# fan.net
KiCad netlist of a schematic drawn in EasyEDA Pro
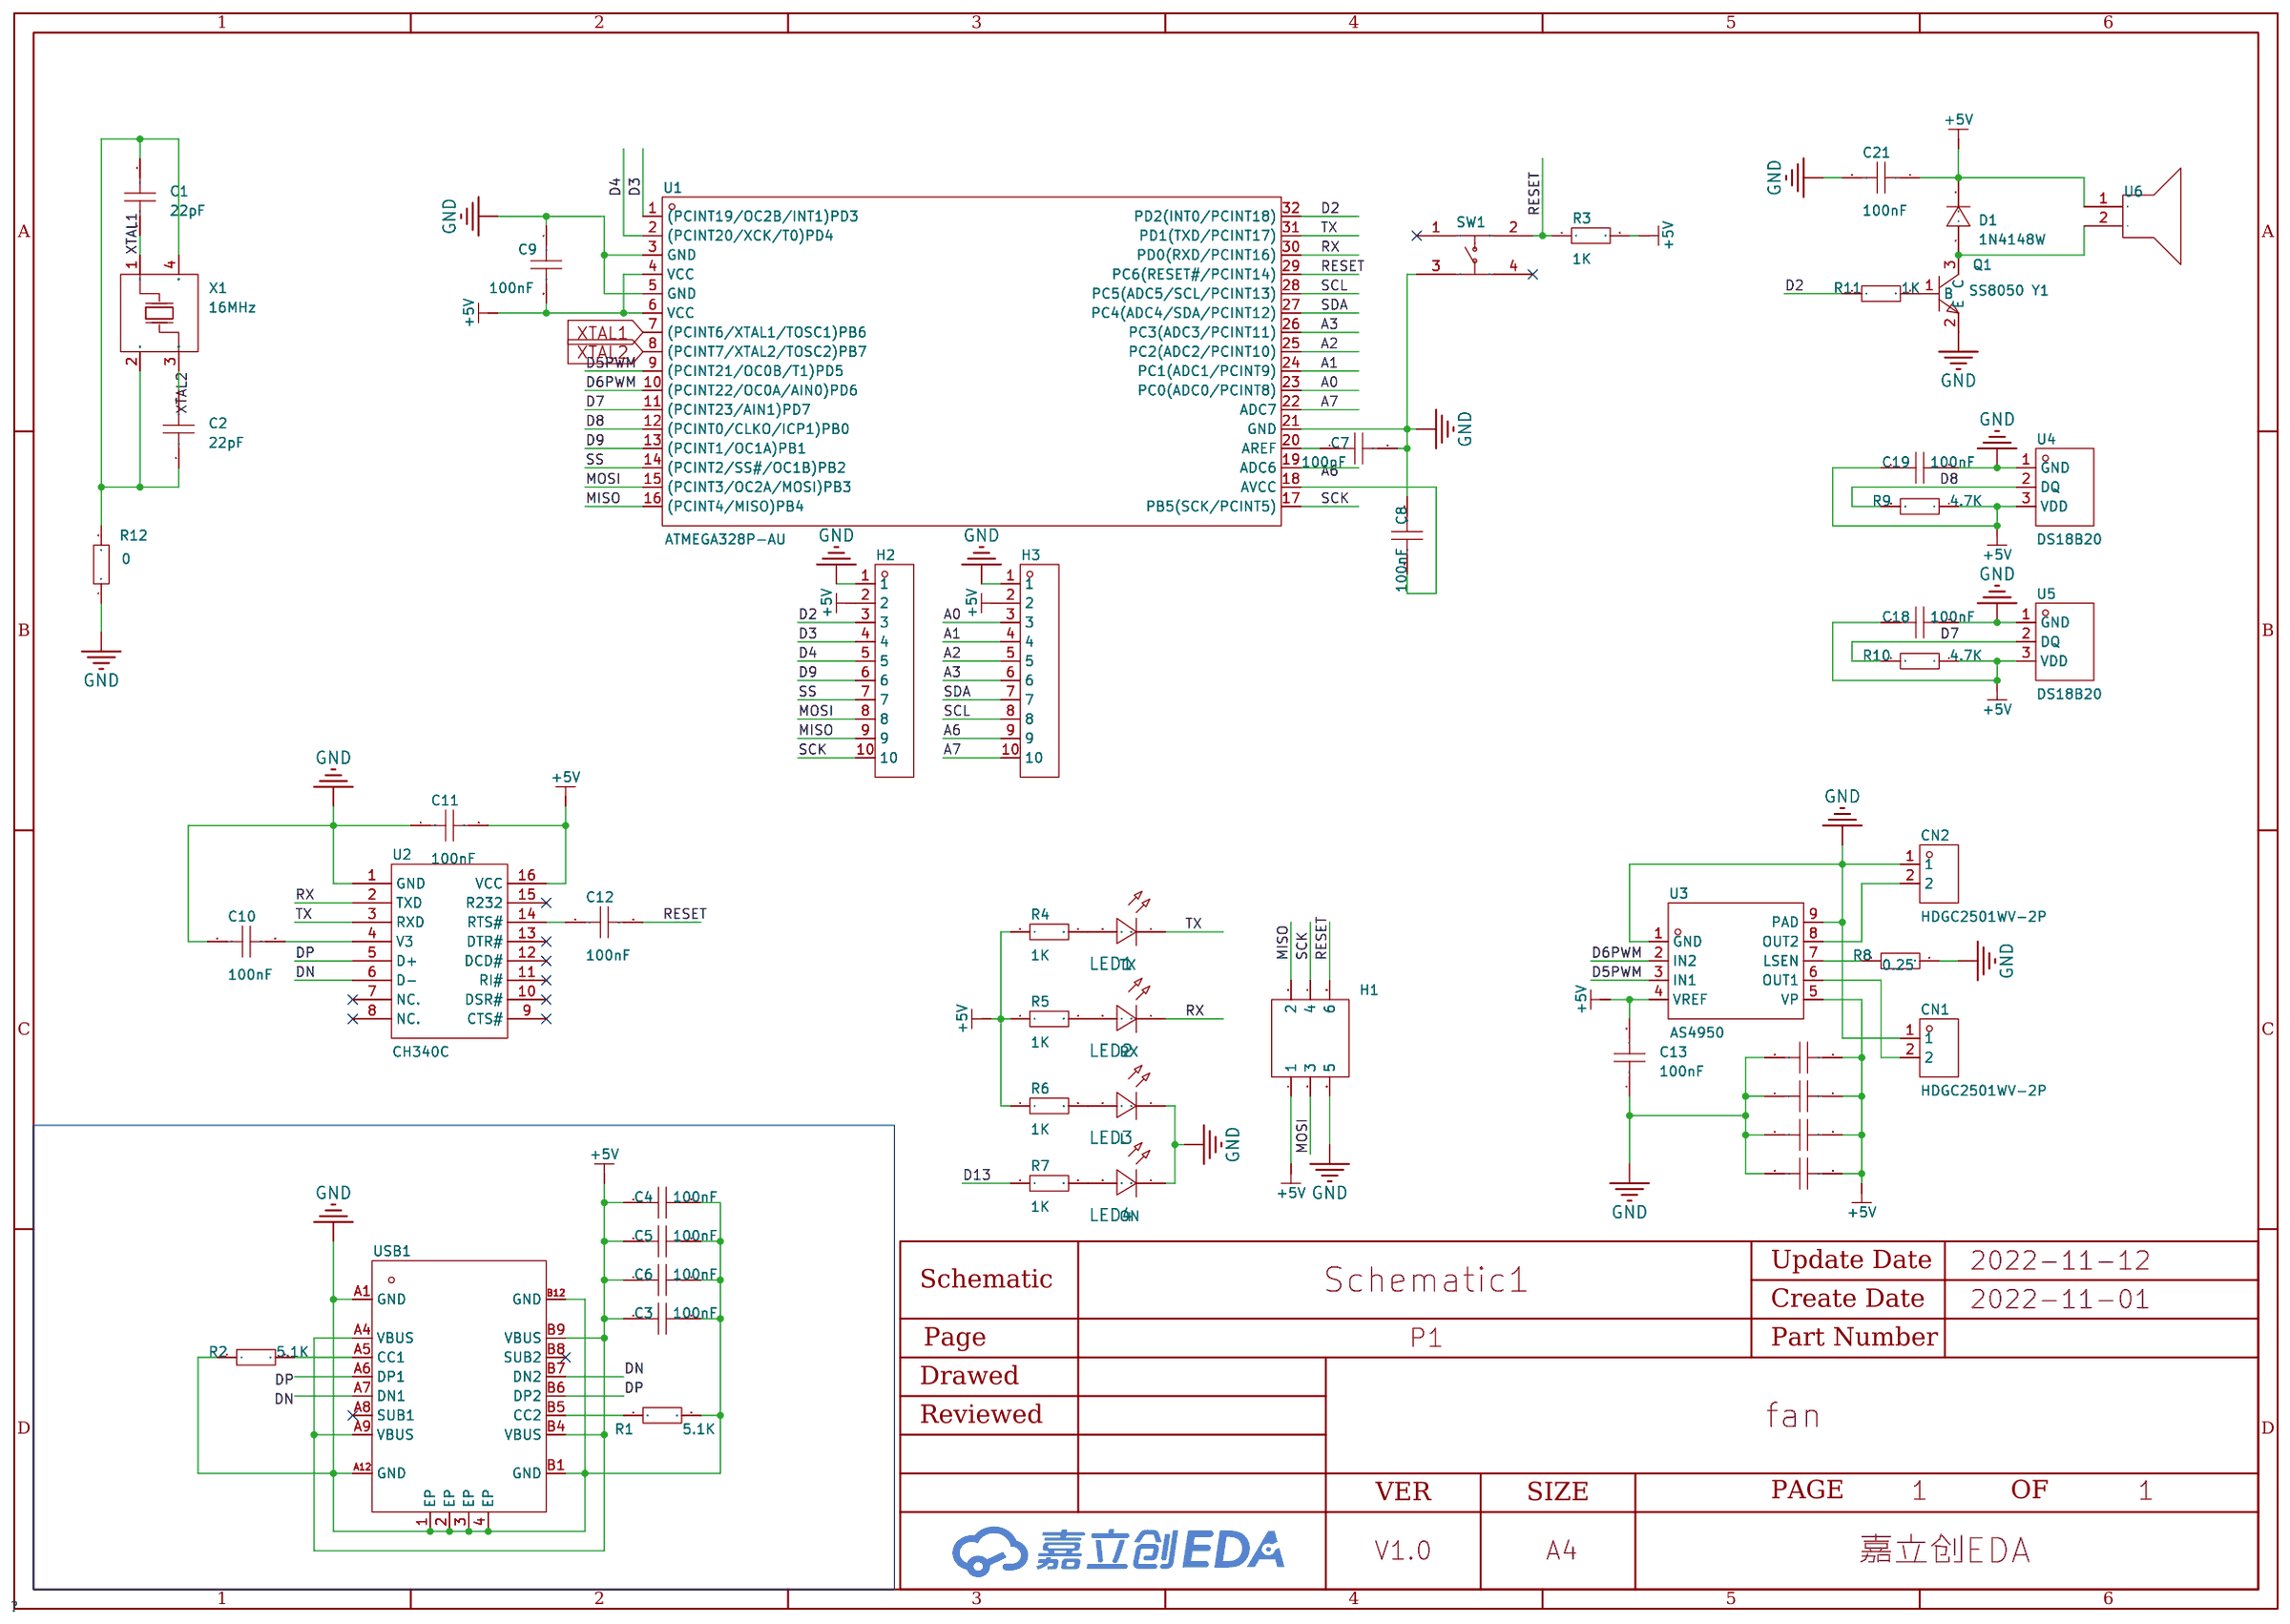
[diagram p0: schematic sheet]

(export (version "E")
  (design (tool "Eeschema 10.0.6"))
  (components
    (comp (ref "C1")
      (value "100nF")
      (footprint "easyedapro:C0603")
      (libsource (lib "easyedapro") (part "C1210X7R475K630NT"))
    )
    (comp (ref "C2")
      (value "100nF")
      (footprint "easyedapro:C0603")
      (libsource (lib "easyedapro") (part "C1210X7R475K630NT"))
    )
    (comp (ref "C3")
      (value "100nF")
      (footprint "easyedapro:C0603")
      (libsource (lib "easyedapro") (part "C1210X7R475K630NT"))
    )
    (comp (ref "C4")
      (value "100nF")
      (footprint "easyedapro:C0603")
      (libsource (lib "easyedapro") (part "C1210X7R475K630NT"))
    )
    (comp (ref "C5")
      (value "100nF")
      (footprint "easyedapro:C0603")
      (libsource (lib "easyedapro") (part "C1210X7R475K630NT"))
    )
    (comp (ref "C6")
      (value "100nF")
      (footprint "easyedapro:C0603")
      (libsource (lib "easyedapro") (part "C1210X7R475K630NT"))
    )
    (comp (ref "C7")
      (value "100nF")
      (footprint "easyedapro:C0603")
      (libsource (lib "easyedapro") (part "C1210X7R475K630NT"))
    )
    (comp (ref "C8")
      (value "100nF")
      (footprint "easyedapro:C0603")
      (libsource (lib "easyedapro") (part "C1210X7R475K630NT"))
    )
    (comp (ref "C9")
      (value "100nF")
      (footprint "easyedapro:C0603")
      (libsource (lib "easyedapro") (part "C1210X7R475K630NT"))
    )
    (comp (ref "C10")
      (value "100nF")
      (footprint "easyedapro:C0603")
      (libsource (lib "easyedapro") (part "C1210X7R475K630NT"))
    )
    (comp (ref "C11")
      (value "100nF")
      (footprint "easyedapro:C0603")
      (libsource (lib "easyedapro") (part "C1210X7R475K630NT"))
    )
    (comp (ref "C12")
      (value "100nF")
      (footprint "easyedapro:C0603")
      (libsource (lib "easyedapro") (part "C1210X7R475K630NT"))
    )
    (comp (ref "C13")
      (value "100nF")
      (footprint "easyedapro:C0603")
      (libsource (lib "easyedapro") (part "C1210X7R475K630NT"))
    )
    (comp (ref "C14")
      (value "100nF")
      (footprint "easyedapro:C0603")
      (libsource (lib "easyedapro") (part "C1210X7R475K630NT"))
    )
    (comp (ref "C15")
      (value "100nF")
      (footprint "easyedapro:C0603")
      (libsource (lib "easyedapro") (part "C1210X7R475K630NT"))
    )
    (comp (ref "C16")
      (value "100nF")
      (footprint "easyedapro:C0603")
      (libsource (lib "easyedapro") (part "C1210X7R475K630NT"))
    )
    (comp (ref "C17")
      (value "100nF")
      (footprint "easyedapro:C0603")
      (libsource (lib "easyedapro") (part "C1210X7R475K630NT"))
    )
    (comp (ref "C18")
      (value "100nF")
      (footprint "easyedapro:C0603")
      (libsource (lib "easyedapro") (part "C1210X7R475K630NT"))
    )
    (comp (ref "C19")
      (value "100nF")
      (footprint "easyedapro:C0603")
      (libsource (lib "easyedapro") (part "C1210X7R475K630NT"))
    )
    (comp (ref "C21")
      (value "100nF")
      (footprint "easyedapro:C0603")
      (libsource (lib "easyedapro") (part "C1210X7R475K630NT"))
    )
    (comp (ref "CN1")
      (value "HDGC2501WV-2P")
      (footprint "easyedapro:CONN-TH_XH2.5-2P")
      (fields (field (name "Manufacturer") "HDGC(华德共创)"))
      (libsource (lib "easyedapro") (part "HDGC2501WV-2P"))
    )
    (comp (ref "CN2")
      (value "HDGC2501WV-2P")
      (footprint "easyedapro:CONN-TH_XH2.5-2P")
      (fields (field (name "Manufacturer") "HDGC(华德共创)"))
      (libsource (lib "easyedapro") (part "HDGC2501WV-2P"))
    )
    (comp (ref "D1")
      (value "1N4148W")
      (footprint "easyedapro:SOD-123_L2.8-W1.8-LS3.7-RD")
      (fields (field (name "Manufacturer") "CJ（江苏长电/长晶）"))
      (libsource (lib "easyedapro") (part "1N4148W T4"))
    )
    (comp (ref "H1")
      (value "~")
      (footprint "easyedapro:HDR-TH_6P-P2.54-V-R2-C3-S2.54_A2541WV-2X3P")
      (libsource (lib "easyedapro") (part "HDR-M-2.54_2x3"))
    )
    (comp (ref "H2")
      (value "~")
      (footprint "easyedapro:HDR-TH_10P-P2.54-V-F")
      (libsource (lib "easyedapro") (part "X5511FV-10-C70D30-1000"))
    )
    (comp (ref "H3")
      (value "~")
      (footprint "easyedapro:HDR-TH_10P-P2.54-V-F")
      (libsource (lib "easyedapro") (part "X5511FV-10-C70D30-1000"))
    )
    (comp (ref "LED1")
      (value "TX")
      (footprint "easyedapro:LED0603-RD_BLUE")
      (libsource (lib "easyedapro") (part "LED_R"))
    )
    (comp (ref "LED2")
      (value "RX")
      (footprint "easyedapro:LED0603-RD_BLUE")
      (libsource (lib "easyedapro") (part "LED_R"))
    )
    (comp (ref "LED3")
      (value "L")
      (footprint "easyedapro:LED0603-RD_BLUE")
      (libsource (lib "easyedapro") (part "LED_R"))
    )
    (comp (ref "LED4")
      (value "ON")
      (footprint "easyedapro:LED0603-RD_BLUE")
      (libsource (lib "easyedapro") (part "LED_R"))
    )
    (comp (ref "Q1")
      (value "SS8050 Y1")
      (footprint "easyedapro:SOT-23-3_L2.9-W1.3-P1.90-LS2.4-BR")
      (fields (field (name "Manufacturer") "FOSAN(富信)"))
      (libsource (lib "easyedapro") (part "SS8050_C2926167"))
    )
    (comp (ref "R1") (value "10K") (footprint "easyedapro:R0603") (libsource (lib "easyedapro") (part "电阻")))
    (comp (ref "R2") (value "10K") (footprint "easyedapro:R0603") (libsource (lib "easyedapro") (part "电阻")))
    (comp (ref "R3") (value "10K") (footprint "easyedapro:R0603") (libsource (lib "easyedapro") (part "电阻")))
    (comp (ref "R4") (value "10K") (footprint "easyedapro:R0603") (libsource (lib "easyedapro") (part "电阻")))
    (comp (ref "R5") (value "10K") (footprint "easyedapro:R0603") (libsource (lib "easyedapro") (part "电阻")))
    (comp (ref "R6") (value "10K") (footprint "easyedapro:R0603") (libsource (lib "easyedapro") (part "电阻")))
    (comp (ref "R7") (value "10K") (footprint "easyedapro:R0603") (libsource (lib "easyedapro") (part "电阻")))
    (comp (ref "R8") (value "10K") (footprint "easyedapro:R0603") (libsource (lib "easyedapro") (part "电阻")))
    (comp (ref "R9") (value "10K") (footprint "easyedapro:R0603") (libsource (lib "easyedapro") (part "电阻")))
    (comp (ref "R10") (value "10K") (footprint "easyedapro:R0603") (libsource (lib "easyedapro") (part "电阻")))
    (comp (ref "R11") (value "10K") (footprint "easyedapro:R0603") (libsource (lib "easyedapro") (part "电阻")))
    (comp (ref "R12") (value "10K") (footprint "easyedapro:R0603") (libsource (lib "easyedapro") (part "电阻")))
    (comp (ref "SW1")
      (value "TSC015A03518A")
      (footprint "easyedapro:KEY-SMD_4P-L4.5-W4.5-P3.00-LS6.9")
      (description "触点电流:50mA;额定电压(AC):12V;额定电压(DC):12V;安装方式:立贴;按钮形状:圆形按钮;开关长度:4.5mm;开关宽度:4.5mm;开关高度:3.5mm;")
      (fields (field (name "Manufacturer") "BZCN(博众电气)"))
      (libsource (lib "easyedapro") (part "TSC015A03518A"))
    )
    (comp (ref "U1")
      (value "ATMEGA328P-AU")
      (footprint "easyedapro:TQFP-32_L7.0-W7.0-P0.80-LS9.0-BL")
      (description "ATmega Series 20 MHz 32 KB Flash 2 KB SRAM 8-Bit Microcontroller - TQFP-32")
      (fields (field (name "Manufacturer") "MICROCHIP(美国微芯)"))
      (libsource (lib "easyedapro") (part "ATMEGA328P-AU"))
    )
    (comp (ref "U2")
      (value "CH340C")
      (footprint "easyedapro:SOP-16_L10.0-W3.9-P1.27-LS6.0-BL")
      (description "类型:Transceiver;协议类别:USB 2.0;驱动器/接收器数:-;数据速率:2Mbps;")
      (fields (field (name "Manufacturer") "WCH(南京沁恒)"))
      (libsource (lib "easyedapro") (part "CH340C"))
    )
    (comp (ref "U3")
      (value "AS4950")
      (footprint "easyedapro:ESOP-8_L4.9-W3.9-P1.27-LS6.0-BL-EP")
      (description "全桥DMOS有刷直流电机驱动器，3.5A峰值驱动输出，8V-40V宽电压供电，支持过流/短路/欠压/过温保护")
      (fields (field (name "Manufacturer") "ASSEMSTAR(聚迹)"))
      (libsource (lib "easyedapro") (part "AS4950"))
    )
    (comp (ref "U4")
      (value "DS18B20")
      (footprint "easyedapro:TO-92-3_L4.9-W3.7-P1.27-L")
      (description "传感器类型:-;输出类型:-;局部感温:-;远程感温:-;分辨率:-;")
      (fields (field (name "Manufacturer") "UMW(友台半导体)"))
      (libsource (lib "easyedapro") (part "DS18B20"))
    )
    (comp (ref "U5")
      (value "DS18B20")
      (footprint "easyedapro:TO-92-3_L4.9-W3.7-P1.27-L")
      (description "传感器类型:-;输出类型:-;局部感温:-;远程感温:-;分辨率:-;")
      (fields (field (name "Manufacturer") "UMW(友台半导体)"))
      (libsource (lib "easyedapro") (part "DS18B20"))
    )
    (comp (ref "U6")
      (value "SFN-1270-0540-35P5.0")
      (footprint "easyedapro:BUZ-TH_BD12.5-P5.00-D0.9")
      (description "驱动方式：无源(外部驱动) 构造类型：压电式 额定电压：5V 频率：4000Hz 声压(SPL)：80dB@5V,10cm 直径(φD)：12.6mm 高度：7.5mm")
      (fields (field (name "Manufacturer") "S&S(海旭)"))
      (libsource (lib "easyedapro") (part "SFN-1270-0540-35P5.0"))
    )
    (comp (ref "USB1")
      (value "~")
      (footprint "easyedapro:USB-C-SMD_KH-TYPE-C-16P")
      (description "连接器类型:Type-C;标准:-;公母:母座;触点数量:16;端口数量:1;安装方式:卧贴;额定电流 - 电源:3A;工作温度范围:-40~+85;")
      (libsource (lib "easyedapro") (part "KH-TYPE-C-16P"))
    )
    (comp (ref "X1")
      (value "16MHz")
      (footprint "easyedapro:CRYSTAL-SMD_4P-L3.2-W2.5-BL")
      (description "晶振类型:SMD 谐振器;频率:16MHz;频率公差:±10ppm;频率稳定度:±50ppm;负载电容:12pF;等效串联电阻(ESR):80Ω;工作温度:-;")
      (fields (field (name "Manufacturer Part") "TAXM16M4RFBCCT2T") (field (name "Manufacturer") "TAE(雅晶鑫)"))
      (libsource (lib "easyedapro") (part "SMD-3225_4P16M12PF10PPM"))
    )
  )
  (nets
    (net (code "1") (name "+5V") (class "Default")
      (node (ref "C11") (pin "2") (pinfunction "2_2") (pintype "input"))
      (node (ref "C13") (pin "2") (pinfunction "2_2") (pintype "input"))
      (node (ref "C14") (pin "2") (pinfunction "2_2") (pintype "input"))
      (node (ref "C15") (pin "2") (pinfunction "2_2") (pintype "input"))
      (node (ref "C16") (pin "2") (pinfunction "2_2") (pintype "input"))
      (node (ref "C17") (pin "2") (pinfunction "2_2") (pintype "input"))
      (node (ref "C18") (pin "1") (pinfunction "1_1") (pintype "input"))
      (node (ref "C19") (pin "1") (pinfunction "1_1") (pintype "input"))
      (node (ref "C21") (pin "1") (pinfunction "1_1") (pintype "input"))
      (node (ref "C3") (pin "1") (pinfunction "1_1") (pintype "input"))
      (node (ref "C4") (pin "1") (pinfunction "1_1") (pintype "input"))
      (node (ref "C5") (pin "1") (pinfunction "1_1") (pintype "input"))
      (node (ref "C6") (pin "1") (pinfunction "1_1") (pintype "input"))
      (node (ref "C9") (pin "2") (pinfunction "2_2") (pintype "input"))
      (node (ref "D1") (pin "1") (pinfunction "K_1") (pintype "input"))
      (node (ref "H1") (pin "1") (pinfunction "1_1") (pintype "input"))
      (node (ref "H2") (pin "2") (pinfunction "2_2") (pintype "input"))
      (node (ref "H3") (pin "2") (pinfunction "2_2") (pintype "input"))
      (node (ref "R10") (pin "1") (pinfunction "1_1") (pintype "input"))
      (node (ref "R3") (pin "2") (pinfunction "2_2") (pintype "input"))
      (node (ref "R4") (pin "1") (pinfunction "1_1") (pintype "input"))
      (node (ref "R5") (pin "1") (pinfunction "1_1") (pintype "input"))
      (node (ref "R6") (pin "1") (pinfunction "1_1") (pintype "input"))
      (node (ref "R9") (pin "1") (pinfunction "1_1") (pintype "input"))
      (node (ref "U1") (pin "4") (pinfunction "VCC_4") (pintype "input"))
      (node (ref "U1") (pin "6") (pinfunction "VCC_6") (pintype "input"))
      (node (ref "U2") (pin "16") (pinfunction "VCC_16") (pintype "input"))
      (node (ref "U3") (pin "4") (pinfunction "VREF_4") (pintype "input"))
      (node (ref "U3") (pin "5") (pinfunction "VP_5") (pintype "input"))
      (node (ref "U4") (pin "3") (pinfunction "VDD_3") (pintype "input"))
      (node (ref "U5") (pin "3") (pinfunction "VDD_3") (pintype "input"))
      (node (ref "U6") (pin "1") (pinfunction "+_1") (pintype "input"))
      (node (ref "USB1") (pin "A4") (pinfunction "VBUS_A4") (pintype "input"))
      (node (ref "USB1") (pin "A9") (pinfunction "VBUS_A9") (pintype "input"))
      (node (ref "USB1") (pin "B4") (pinfunction "VBUS_B4") (pintype "input"))
      (node (ref "USB1") (pin "B9") (pinfunction "VBUS_B9") (pintype "input"))
    )
    (net (code "2") (name "/A0") (class "Default")
      (node (ref "H3") (pin "3") (pinfunction "3_3") (pintype "input"))
      (node (ref "U1") (pin "23") (pinfunction "PC0(ADC0/PCINT8)_23") (pintype "input"))
    )
    (net (code "3") (name "/A1") (class "Default")
      (node (ref "H3") (pin "4") (pinfunction "4_4") (pintype "input"))
      (node (ref "U1") (pin "24") (pinfunction "PC1(ADC1/PCINT9)_24") (pintype "input"))
    )
    (net (code "4") (name "/A2") (class "Default")
      (node (ref "H3") (pin "5") (pinfunction "5_5") (pintype "input"))
      (node (ref "U1") (pin "25") (pinfunction "PC2(ADC2/PCINT10)_25") (pintype "input"))
    )
    (net (code "5") (name "/A3") (class "Default")
      (node (ref "H3") (pin "6") (pinfunction "6_6") (pintype "input"))
      (node (ref "U1") (pin "26") (pinfunction "PC3(ADC3/PCINT11)_26") (pintype "input"))
    )
    (net (code "6") (name "/A6") (class "Default")
      (node (ref "H3") (pin "9") (pinfunction "9_9") (pintype "input"))
      (node (ref "U1") (pin "19") (pinfunction "ADC6_19") (pintype "input"))
    )
    (net (code "7") (name "/A7") (class "Default")
      (node (ref "H3") (pin "10") (pinfunction "10_10") (pintype "input"))
      (node (ref "U1") (pin "22") (pinfunction "ADC7_22") (pintype "input"))
    )
    (net (code "8") (name "/D2") (class "Default")
      (node (ref "H2") (pin "3") (pinfunction "3_3") (pintype "input"))
      (node (ref "R11") (pin "1") (pinfunction "1_1") (pintype "input"))
      (node (ref "U1") (pin "32") (pinfunction "PD2(INT0/PCINT18)_32") (pintype "input"))
    )
    (net (code "9") (name "/D3") (class "Default")
      (node (ref "H2") (pin "4") (pinfunction "4_4") (pintype "input"))
      (node (ref "U1") (pin "1") (pinfunction "(PCINT19/OC2B/INT1)PD3_1") (pintype "input"))
    )
    (net (code "10") (name "/D4") (class "Default")
      (node (ref "H2") (pin "5") (pinfunction "5_5") (pintype "input"))
      (node (ref "U1") (pin "2") (pinfunction "(PCINT20/XCK/T0)PD4_2") (pintype "input"))
    )
    (net (code "11") (name "/D5PWM") (class "Default")
      (node (ref "U1") (pin "9") (pinfunction "(PCINT21/OC0B/T1)PD5_9") (pintype "input"))
      (node (ref "U3") (pin "3") (pinfunction "IN1_3") (pintype "input"))
    )
    (net (code "12") (name "/D6PWM") (class "Default")
      (node (ref "U1") (pin "10") (pinfunction "(PCINT22/OC0A/AIN0)PD6_10") (pintype "input"))
      (node (ref "U3") (pin "2") (pinfunction "IN2_2") (pintype "input"))
    )
    (net (code "13") (name "/D7") (class "Default")
      (node (ref "R10") (pin "2") (pinfunction "2_2") (pintype "input"))
      (node (ref "U1") (pin "11") (pinfunction "(PCINT23/AIN1)PD7_11") (pintype "input"))
      (node (ref "U5") (pin "2") (pinfunction "DQ_2") (pintype "input"))
    )
    (net (code "14") (name "/D8") (class "Default")
      (node (ref "R9") (pin "2") (pinfunction "2_2") (pintype "input"))
      (node (ref "U1") (pin "12") (pinfunction "(PCINT0/CLKO/ICP1)PB0_12") (pintype "input"))
      (node (ref "U4") (pin "2") (pinfunction "DQ_2") (pintype "input"))
    )
    (net (code "15") (name "/D9") (class "Default")
      (node (ref "H2") (pin "6") (pinfunction "6_6") (pintype "input"))
      (node (ref "U1") (pin "13") (pinfunction "(PCINT1/OC1A)PB1_13") (pintype "input"))
    )
    (net (code "16") (name "/D13") (class "Default")
      (node (ref "R7") (pin "1") (pinfunction "1_1") (pintype "input"))
    )
    (net (code "17") (name "/DN") (class "Default")
      (node (ref "U2") (pin "6") (pinfunction "D-_6") (pintype "input"))
      (node (ref "USB1") (pin "A7") (pinfunction "DN1_A7") (pintype "input"))
      (node (ref "USB1") (pin "B7") (pinfunction "DN2_B7") (pintype "input"))
    )
    (net (code "18") (name "/DP") (class "Default")
      (node (ref "U2") (pin "5") (pinfunction "D+_5") (pintype "input"))
      (node (ref "USB1") (pin "A6") (pinfunction "DP1_A6") (pintype "input"))
      (node (ref "USB1") (pin "B6") (pinfunction "DP2_B6") (pintype "input"))
    )
    (net (code "19") (name "/MISO") (class "Default")
      (node (ref "H1") (pin "2") (pinfunction "2_2") (pintype "input"))
      (node (ref "H2") (pin "9") (pinfunction "9_9") (pintype "input"))
      (node (ref "U1") (pin "16") (pinfunction "(PCINT4/MISO)PB4_16") (pintype "input"))
    )
    (net (code "20") (name "/MOSI") (class "Default")
      (node (ref "H1") (pin "3") (pinfunction "3_3") (pintype "input"))
      (node (ref "H2") (pin "8") (pinfunction "8_8") (pintype "input"))
      (node (ref "U1") (pin "15") (pinfunction "(PCINT3/OC2A/MOSI)PB3_15") (pintype "input"))
    )
    (net (code "21") (name "/RESET") (class "Default")
      (node (ref "C12") (pin "2") (pinfunction "2_2") (pintype "input"))
      (node (ref "H1") (pin "6") (pinfunction "6_6") (pintype "input"))
      (node (ref "R3") (pin "1") (pinfunction "1_1") (pintype "input"))
      (node (ref "SW1") (pin "2") (pinfunction "2_2") (pintype "input"))
      (node (ref "U1") (pin "29") (pinfunction "PC6(RESET#/PCINT14)_29") (pintype "input"))
    )
    (net (code "22") (name "/RX") (class "Default")
      (node (ref "LED2") (pin "1") (pinfunction "C_1") (pintype "input"))
      (node (ref "U1") (pin "30") (pinfunction "PD0(RXD/PCINT16)_30") (pintype "input"))
      (node (ref "U2") (pin "2") (pinfunction "TXD_2") (pintype "input"))
    )
    (net (code "23") (name "/SCK") (class "Default")
      (node (ref "H1") (pin "4") (pinfunction "4_4") (pintype "input"))
      (node (ref "H2") (pin "10") (pinfunction "10_10") (pintype "input"))
      (node (ref "U1") (pin "17") (pinfunction "PB5(SCK/PCINT5)_17") (pintype "input"))
    )
    (net (code "24") (name "/SCL") (class "Default")
      (node (ref "H3") (pin "8") (pinfunction "8_8") (pintype "input"))
      (node (ref "U1") (pin "28") (pinfunction "PC5(ADC5/SCL/PCINT13)_28") (pintype "input"))
    )
    (net (code "25") (name "/SDA") (class "Default")
      (node (ref "H3") (pin "7") (pinfunction "7_7") (pintype "input"))
      (node (ref "U1") (pin "27") (pinfunction "PC4(ADC4/SDA/PCINT12)_27") (pintype "input"))
    )
    (net (code "26") (name "/SS") (class "Default")
      (node (ref "H2") (pin "7") (pinfunction "7_7") (pintype "input"))
      (node (ref "U1") (pin "14") (pinfunction "(PCINT2/SS#/OC1B)PB2_14") (pintype "input"))
    )
    (net (code "27") (name "/TX") (class "Default")
      (node (ref "LED1") (pin "1") (pinfunction "C_1") (pintype "input"))
      (node (ref "U1") (pin "31") (pinfunction "PD1(TXD/PCINT17)_31") (pintype "input"))
      (node (ref "U2") (pin "3") (pinfunction "RXD_3") (pintype "input"))
    )
    (net (code "28") (name "GND") (class "Default")
      (node (ref "C10") (pin "1") (pinfunction "1_1") (pintype "input"))
      (node (ref "C11") (pin "1") (pinfunction "1_1") (pintype "input"))
      (node (ref "C13") (pin "1") (pinfunction "1_1") (pintype "input"))
      (node (ref "C14") (pin "1") (pinfunction "1_1") (pintype "input"))
      (node (ref "C15") (pin "1") (pinfunction "1_1") (pintype "input"))
      (node (ref "C16") (pin "1") (pinfunction "1_1") (pintype "input"))
      (node (ref "C17") (pin "1") (pinfunction "1_1") (pintype "input"))
      (node (ref "C18") (pin "2") (pinfunction "2_2") (pintype "input"))
      (node (ref "C19") (pin "2") (pinfunction "2_2") (pintype "input"))
      (node (ref "C21") (pin "2") (pinfunction "2_2") (pintype "input"))
      (node (ref "C3") (pin "2") (pinfunction "2_2") (pintype "input"))
      (node (ref "C4") (pin "2") (pinfunction "2_2") (pintype "input"))
      (node (ref "C5") (pin "2") (pinfunction "2_2") (pintype "input"))
      (node (ref "C6") (pin "2") (pinfunction "2_2") (pintype "input"))
      (node (ref "C7") (pin "2") (pinfunction "2_2") (pintype "input"))
      (node (ref "C8") (pin "2") (pinfunction "2_2") (pintype "input"))
      (node (ref "C9") (pin "1") (pinfunction "1_1") (pintype "input"))
      (node (ref "CN1") (pin "1") (pinfunction "1_1") (pintype "input"))
      (node (ref "CN2") (pin "1") (pinfunction "1_1") (pintype "input"))
      (node (ref "H1") (pin "5") (pinfunction "5_5") (pintype "input"))
      (node (ref "H2") (pin "1") (pinfunction "1_1") (pintype "input"))
      (node (ref "H3") (pin "1") (pinfunction "1_1") (pintype "input"))
      (node (ref "LED3") (pin "1") (pinfunction "C_1") (pintype "input"))
      (node (ref "LED4") (pin "1") (pinfunction "C_1") (pintype "input"))
      (node (ref "Q1") (pin "2") (pinfunction "E_2") (pintype "input"))
      (node (ref "R1") (pin "2") (pinfunction "2_2") (pintype "input"))
      (node (ref "R12") (pin "1") (pinfunction "1_1") (pintype "input"))
      (node (ref "R2") (pin "1") (pinfunction "1_1") (pintype "input"))
      (node (ref "R8") (pin "2") (pinfunction "2_2") (pintype "input"))
      (node (ref "SW1") (pin "3") (pinfunction "3_3") (pintype "input"))
      (node (ref "U1") (pin "21") (pinfunction "GND_21") (pintype "input"))
      (node (ref "U1") (pin "3") (pinfunction "GND_3") (pintype "input"))
      (node (ref "U1") (pin "5") (pinfunction "GND_5") (pintype "input"))
      (node (ref "U2") (pin "1") (pinfunction "GND_1") (pintype "input"))
      (node (ref "U3") (pin "1") (pinfunction "GND_1") (pintype "input"))
      (node (ref "U3") (pin "9") (pinfunction "PAD_9") (pintype "input"))
      (node (ref "U4") (pin "1") (pinfunction "GND_1") (pintype "input"))
      (node (ref "U5") (pin "1") (pinfunction "GND_1") (pintype "input"))
      (node (ref "USB1") (pin "1") (pinfunction "EP_1") (pintype "input"))
      (node (ref "USB1") (pin "2") (pinfunction "EP_2") (pintype "input"))
      (node (ref "USB1") (pin "3") (pinfunction "EP_3") (pintype "input"))
      (node (ref "USB1") (pin "4") (pinfunction "EP_4") (pintype "input"))
      (node (ref "USB1") (pin "A1") (pinfunction "GND_A1") (pintype "input"))
      (node (ref "USB1") (pin "A12") (pinfunction "GND_A12") (pintype "input"))
      (node (ref "USB1") (pin "B1") (pinfunction "GND_B1") (pintype "input"))
      (node (ref "USB1") (pin "B12") (pinfunction "GND_B12") (pintype "input"))
    )
    (net (code "29") (name "Net-(C1-Pad2)") (class "Default")
      (node (ref "C1") (pin "2") (pinfunction "2_2") (pintype "input"))
      (node (ref "C2") (pin "1") (pinfunction "1_1") (pintype "input"))
      (node (ref "R12") (pin "2") (pinfunction "2_2") (pintype "input"))
      (node (ref "X1") (pin "2") (pinfunction "GND_2") (pintype "input"))
      (node (ref "X1") (pin "4") (pinfunction "GND_4") (pintype "input"))
    )
    (net (code "30") (name "Net-(D1-A)") (class "Default")
      (node (ref "D1") (pin "2") (pinfunction "A_2") (pintype "input"))
      (node (ref "Q1") (pin "3") (pinfunction "C_3") (pintype "input"))
      (node (ref "U6") (pin "2") (pinfunction "-_2") (pintype "input"))
    )
    (net (code "31") (name "Net-(LED1-A)") (class "Default")
      (node (ref "LED1") (pin "2") (pinfunction "A_2") (pintype "input"))
      (node (ref "R4") (pin "2") (pinfunction "2_2") (pintype "input"))
    )
    (net (code "32") (name "Net-(LED2-A)") (class "Default")
      (node (ref "LED2") (pin "2") (pinfunction "A_2") (pintype "input"))
      (node (ref "R5") (pin "2") (pinfunction "2_2") (pintype "input"))
    )
    (net (code "33") (name "Net-(LED3-A)") (class "Default")
      (node (ref "LED3") (pin "2") (pinfunction "A_2") (pintype "input"))
      (node (ref "R6") (pin "2") (pinfunction "2_2") (pintype "input"))
    )
    (net (code "34") (name "Net-(LED4-A)") (class "Default")
      (node (ref "LED4") (pin "2") (pinfunction "A_2") (pintype "input"))
      (node (ref "R7") (pin "2") (pinfunction "2_2") (pintype "input"))
    )
    (net (code "35") (name "Net-(Q1-B)") (class "Default")
      (node (ref "Q1") (pin "1") (pinfunction "B_1") (pintype "input"))
      (node (ref "R11") (pin "2") (pinfunction "2_2") (pintype "input"))
    )
    (net (code "36") (name "Net-(U1-AREF)") (class "Default")
      (node (ref "C7") (pin "1") (pinfunction "1_1") (pintype "input"))
      (node (ref "U1") (pin "20") (pinfunction "AREF_20") (pintype "input"))
    )
    (net (code "37") (name "Net-(U1-AVCC)") (class "Default")
      (node (ref "C8") (pin "1") (pinfunction "1_1") (pintype "input"))
      (node (ref "U1") (pin "18") (pinfunction "AVCC_18") (pintype "input"))
    )
    (net (code "38") (name "Net-(U2-RTS#)") (class "Default")
      (node (ref "C12") (pin "1") (pinfunction "1_1") (pintype "input"))
      (node (ref "U2") (pin "14") (pinfunction "RTS#_14") (pintype "input"))
    )
    (net (code "39") (name "Net-(U2-V3)") (class "Default")
      (node (ref "C10") (pin "2") (pinfunction "2_2") (pintype "input"))
      (node (ref "U2") (pin "4") (pinfunction "V3_4") (pintype "input"))
    )
    (net (code "40") (name "Net-(U3-LSEN)") (class "Default")
      (node (ref "R8") (pin "1") (pinfunction "1_1") (pintype "input"))
      (node (ref "U3") (pin "7") (pinfunction "LSEN_7") (pintype "input"))
    )
    (net (code "41") (name "Net-(U3-OUT1)") (class "Default")
      (node (ref "CN1") (pin "2") (pinfunction "2_2") (pintype "input"))
      (node (ref "U3") (pin "6") (pinfunction "OUT1_6") (pintype "input"))
    )
    (net (code "42") (name "Net-(U3-OUT2)") (class "Default")
      (node (ref "CN2") (pin "2") (pinfunction "2_2") (pintype "input"))
      (node (ref "U3") (pin "8") (pinfunction "OUT2_8") (pintype "input"))
    )
    (net (code "43") (name "Net-(USB1-CC1)") (class "Default")
      (node (ref "R2") (pin "2") (pinfunction "2_2") (pintype "input"))
      (node (ref "USB1") (pin "A5") (pinfunction "CC1_A5") (pintype "input"))
    )
    (net (code "44") (name "Net-(USB1-CC2)") (class "Default")
      (node (ref "R1") (pin "1") (pinfunction "1_1") (pintype "input"))
      (node (ref "USB1") (pin "B5") (pinfunction "CC2_B5") (pintype "input"))
    )
    (net (code "45") (name "XTAL1") (class "Default")
      (node (ref "C1") (pin "1") (pinfunction "1_1") (pintype "input"))
      (node (ref "U1") (pin "7") (pinfunction "(PCINT6/XTAL1/TOSC1)PB6_7") (pintype "input"))
      (node (ref "X1") (pin "1") (pinfunction "OSC1_1") (pintype "input"))
    )
    (net (code "46") (name "XTAL2") (class "Default")
      (node (ref "C2") (pin "2") (pinfunction "2_2") (pintype "input"))
      (node (ref "U1") (pin "8") (pinfunction "(PCINT7/XTAL2/TOSC2)PB7_8") (pintype "input"))
      (node (ref "X1") (pin "3") (pinfunction "OSC2_3") (pintype "input"))
    )
    (net (code "47") (name "unconnected-(SW1-Pad1)") (class "Default")
      (node (ref "SW1") (pin "1") (pinfunction "1_1") (pintype "input+no_connect"))
    )
    (net (code "48") (name "unconnected-(SW1-Pad4)") (class "Default")
      (node (ref "SW1") (pin "4") (pinfunction "4_4") (pintype "input+no_connect"))
    )
    (net (code "49") (name "unconnected-(U2-CTS#-Pad9)") (class "Default")
      (node (ref "U2") (pin "9") (pinfunction "CTS#_9") (pintype "input+no_connect"))
    )
    (net (code "50") (name "unconnected-(U2-DCD#-Pad12)") (class "Default")
      (node (ref "U2") (pin "12") (pinfunction "DCD#_12") (pintype "input+no_connect"))
    )
    (net (code "51") (name "unconnected-(U2-DSR#-Pad10)") (class "Default")
      (node (ref "U2") (pin "10") (pinfunction "DSR#_10") (pintype "input+no_connect"))
    )
    (net (code "52") (name "unconnected-(U2-DTR#-Pad13)") (class "Default")
      (node (ref "U2") (pin "13") (pinfunction "DTR#_13") (pintype "input+no_connect"))
    )
    (net (code "53") (name "unconnected-(U2-NC.-Pad7)") (class "Default")
      (node (ref "U2") (pin "7") (pinfunction "NC._7") (pintype "input+no_connect"))
    )
    (net (code "54") (name "unconnected-(U2-NC.-Pad8)") (class "Default")
      (node (ref "U2") (pin "8") (pinfunction "NC._8") (pintype "input+no_connect"))
    )
    (net (code "55") (name "unconnected-(U2-R232-Pad15)") (class "Default")
      (node (ref "U2") (pin "15") (pinfunction "R232_15") (pintype "input+no_connect"))
    )
    (net (code "56") (name "unconnected-(U2-RI#-Pad11)") (class "Default")
      (node (ref "U2") (pin "11") (pinfunction "RI#_11") (pintype "input+no_connect"))
    )
    (net (code "57") (name "unconnected-(USB1-SUB1-PadA8)") (class "Default")
      (node (ref "USB1") (pin "A8") (pinfunction "SUB1_A8") (pintype "input+no_connect"))
    )
    (net (code "58") (name "unconnected-(USB1-SUB2-PadB8)") (class "Default")
      (node (ref "USB1") (pin "B8") (pinfunction "SUB2_B8") (pintype "input+no_connect"))
    )
  )
)
